# ProPrj_usb__2025-12-14-12-19-49.net
KiCad netlist of a schematic drawn in EasyEDA Pro
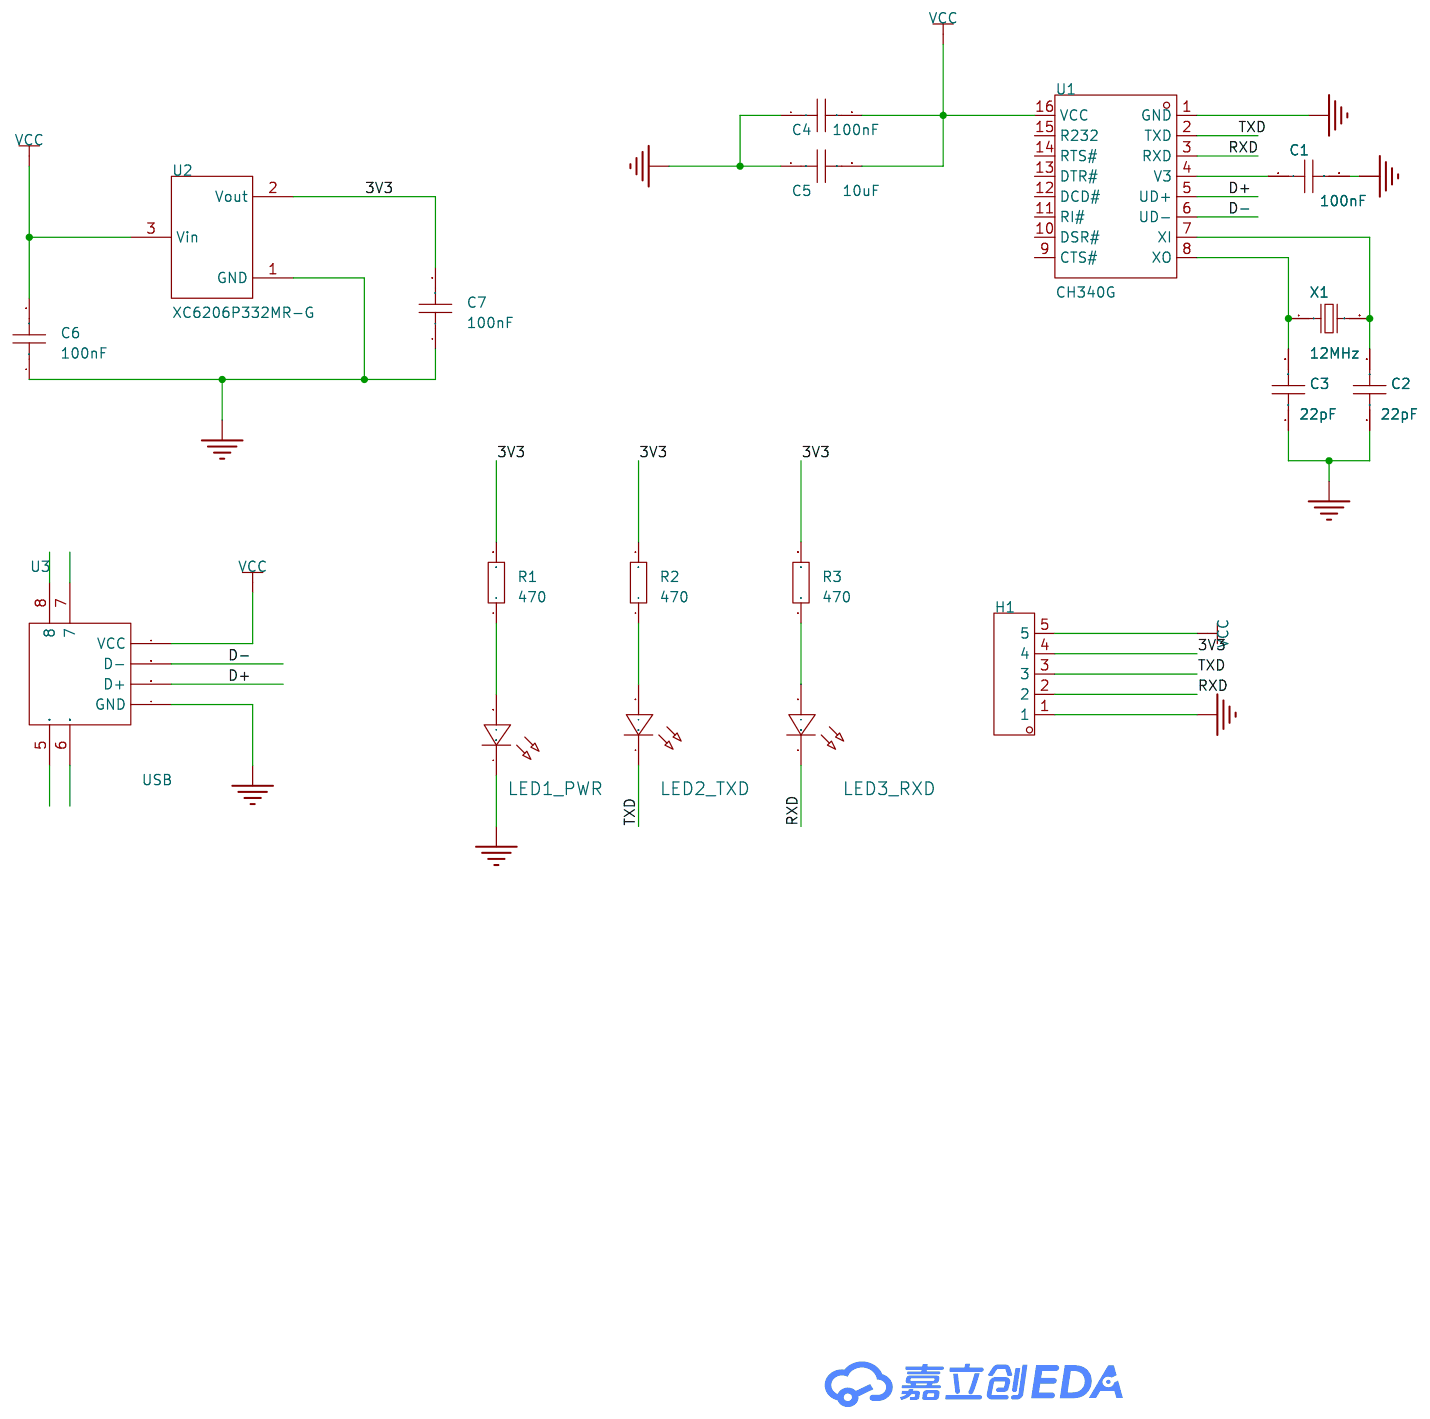
[diagram p0: schematic sheet]

(export (version "E")
  (design (tool "Eeschema 10.0.6"))
  (components
    (comp (ref "C1")
      (value "100nF")
      (footprint "easyedapro:C0603")
      (libsource (lib "easyedapro") (part "Capacitance"))
    )
    (comp (ref "C2")
      (value "22pF")
      (footprint "easyedapro:C0603")
      (libsource (lib "easyedapro") (part "Capacitance"))
    )
    (comp (ref "C3")
      (value "22pF")
      (footprint "easyedapro:C0603")
      (libsource (lib "easyedapro") (part "Capacitance"))
    )
    (comp (ref "C4")
      (value "100nF")
      (footprint "easyedapro:C0603")
      (libsource (lib "easyedapro") (part "Capacitance"))
    )
    (comp (ref "C5")
      (value "10uF")
      (footprint "easyedapro:C0603")
      (libsource (lib "easyedapro") (part "Capacitance"))
    )
    (comp (ref "C6")
      (value "100nF")
      (footprint "easyedapro:C0603")
      (libsource (lib "easyedapro") (part "Capacitance"))
    )
    (comp (ref "C7")
      (value "100nF")
      (footprint "easyedapro:C0603")
      (libsource (lib "easyedapro") (part "Capacitance"))
    )
    (comp (ref "H1")
      (value "~")
      (footprint "easyedapro:HDR-TH_5P-P2.54-V-M")
      (libsource (lib "easyedapro") (part "MTP125-1105S1"))
    )
    (comp (ref "LED1_PWR")
      (value "~")
      (footprint "easyedapro:LED_0603")
      (libsource (lib "easyedapro") (part "LED_R"))
    )
    (comp (ref "LED2_TXD")
      (value "~")
      (footprint "easyedapro:LED_0603")
      (libsource (lib "easyedapro") (part "LED_R"))
    )
    (comp (ref "LED3_RXD")
      (value "~")
      (footprint "easyedapro:LED_0603")
      (libsource (lib "easyedapro") (part "LED_R"))
    )
    (comp (ref "R1") (value "470") (footprint "easyedapro:R0603") (libsource (lib "easyedapro") (part "电阻")))
    (comp (ref "R2") (value "470") (footprint "easyedapro:R0603") (libsource (lib "easyedapro") (part "电阻")))
    (comp (ref "R3") (value "470") (footprint "easyedapro:R0603") (libsource (lib "easyedapro") (part "电阻")))
    (comp (ref "U1")
      (value "CH340G")
      (footprint "easyedapro:SOIC-16_L9.9-W3.9-P1.27-LS6.0-BL")
      (description "应用功能:USB转UART;接口协议:USB 2.0;数据速率:2Mbps;")
      (fields (field (name "Manufacturer") "WCH(南京沁恒)"))
      (libsource (lib "easyedapro") (part "CH340G"))
    )
    (comp (ref "U2")
      (value "XC6206P332MR-G")
      (footprint "easyedapro:SOT-23-3_L2.9-W1.6-P1.90-LS2.8-BR")
      (description "输出类型:固定;工作电压:6V;输出电压:3.3V;输出电流:200mA;电源纹波抑制比(PSRR):-;输出极性:正极;")
      (fields (field (name "Manufacturer") "TOREX(特瑞仕)"))
      (libsource (lib "easyedapro") (part "XC6206P332MR"))
    )
    (comp (ref "U3")
      (value "USB")
      (footprint "easyedapro:USB-SMD_USB_1")
      (libsource (lib "easyedapro") (part "USB"))
    )
    (comp (ref "X1")
      (value "12MHz")
      (footprint "easyedapro:CRYSTAL-SMD_L5.0-W3.2")
      (description "晶振类型:贴片晶振;频率:12MHz;常温频差:±20ppm;负载电容:20pF;频率稳定度:±30ppm;")
      (fields
        (field (name "Manufacturer Part") "XC53G2-12.000-F20LJDT")
        (field (name "Manufacturer") "HCI(杭晶)")
      )
      (libsource (lib "easyedapro") (part "XC53G2-12.000-F20LJDT"))
    )
  )
  (nets
    (net (code "1") (name "/3V3") (class "Default")
      (node (ref "C7") (pin "2") (pinfunction "2_2") (pintype "input"))
      (node (ref "H1") (pin "4") (pinfunction "4_4") (pintype "unspecified"))
      (node (ref "R1") (pin "2") (pinfunction "2_2") (pintype "input"))
      (node (ref "R2") (pin "2") (pinfunction "2_2") (pintype "input"))
      (node (ref "R3") (pin "2") (pinfunction "2_2") (pintype "input"))
      (node (ref "U2") (pin "2") (pinfunction "Vout_2") (pintype "unspecified"))
    )
    (net (code "2") (name "/D+") (class "Default")
      (node (ref "U1") (pin "5") (pinfunction "UD+_5") (pintype "unspecified"))
      (node (ref "U3") (pin "3") (pinfunction "D+_3") (pintype "input"))
    )
    (net (code "3") (name "/D-") (class "Default")
      (node (ref "U1") (pin "6") (pinfunction "UD-_6") (pintype "unspecified"))
      (node (ref "U3") (pin "2") (pinfunction "D-_2") (pintype "input"))
    )
    (net (code "4") (name "/RXD") (class "Default")
      (node (ref "H1") (pin "2") (pinfunction "2_2") (pintype "unspecified"))
      (node (ref "LED3_RXD") (pin "1") (pinfunction "C_1") (pintype "input"))
      (node (ref "U1") (pin "3") (pinfunction "RXD_3") (pintype "unspecified"))
    )
    (net (code "5") (name "/TXD") (class "Default")
      (node (ref "H1") (pin "3") (pinfunction "3_3") (pintype "unspecified"))
      (node (ref "LED2_TXD") (pin "1") (pinfunction "C_1") (pintype "input"))
      (node (ref "U1") (pin "2") (pinfunction "TXD_2") (pintype "unspecified"))
    )
    (net (code "6") (name "GND") (class "Default")
      (node (ref "C1") (pin "2") (pinfunction "2_2") (pintype "input"))
      (node (ref "C2") (pin "1") (pinfunction "1_1") (pintype "input"))
      (node (ref "C3") (pin "1") (pinfunction "1_1") (pintype "input"))
      (node (ref "C4") (pin "1") (pinfunction "1_1") (pintype "input"))
      (node (ref "C5") (pin "1") (pinfunction "1_1") (pintype "input"))
      (node (ref "C6") (pin "1") (pinfunction "1_1") (pintype "input"))
      (node (ref "C7") (pin "1") (pinfunction "1_1") (pintype "input"))
      (node (ref "H1") (pin "1") (pinfunction "1_1") (pintype "unspecified"))
      (node (ref "LED1_PWR") (pin "1") (pinfunction "C_1") (pintype "input"))
      (node (ref "U1") (pin "1") (pinfunction "GND_1") (pintype "unspecified"))
      (node (ref "U2") (pin "1") (pinfunction "GND_1") (pintype "unspecified"))
      (node (ref "U3") (pin "4") (pinfunction "GND_4") (pintype "input"))
    )
    (net (code "7") (name "Net-(LED1_PWR-A)") (class "Default")
      (node (ref "LED1_PWR") (pin "2") (pinfunction "A_2") (pintype "input"))
      (node (ref "R1") (pin "1") (pinfunction "1_1") (pintype "input"))
    )
    (net (code "8") (name "Net-(LED2_TXD-A)") (class "Default")
      (node (ref "LED2_TXD") (pin "2") (pinfunction "A_2") (pintype "input"))
      (node (ref "R2") (pin "1") (pinfunction "1_1") (pintype "input"))
    )
    (net (code "9") (name "Net-(LED3_RXD-A)") (class "Default")
      (node (ref "LED3_RXD") (pin "2") (pinfunction "A_2") (pintype "input"))
      (node (ref "R3") (pin "1") (pinfunction "1_1") (pintype "input"))
    )
    (net (code "10") (name "Net-(U1-V3)") (class "Default")
      (node (ref "C1") (pin "1") (pinfunction "1_1") (pintype "input"))
      (node (ref "U1") (pin "4") (pinfunction "V3_4") (pintype "unspecified"))
    )
    (net (code "11") (name "Net-(U1-XI)") (class "Default")
      (node (ref "C2") (pin "2") (pinfunction "2_2") (pintype "input"))
      (node (ref "U1") (pin "7") (pinfunction "XI_7") (pintype "unspecified"))
      (node (ref "X1") (pin "2") (pinfunction "2_2") (pintype "unspecified"))
    )
    (net (code "12") (name "Net-(U1-XO)") (class "Default")
      (node (ref "C3") (pin "2") (pinfunction "2_2") (pintype "input"))
      (node (ref "U1") (pin "8") (pinfunction "XO_8") (pintype "unspecified"))
      (node (ref "X1") (pin "1") (pinfunction "1_1") (pintype "unspecified"))
    )
    (net (code "13") (name "VCC") (class "Default")
      (node (ref "C4") (pin "2") (pinfunction "2_2") (pintype "input"))
      (node (ref "C5") (pin "2") (pinfunction "2_2") (pintype "input"))
      (node (ref "C6") (pin "2") (pinfunction "2_2") (pintype "input"))
      (node (ref "H1") (pin "5") (pinfunction "5_5") (pintype "unspecified"))
      (node (ref "U1") (pin "16") (pinfunction "VCC_16") (pintype "unspecified"))
      (node (ref "U2") (pin "3") (pinfunction "Vin_3") (pintype "unspecified"))
      (node (ref "U3") (pin "1") (pinfunction "VCC_1") (pintype "input"))
    )
    (net (code "14") (name "unconnected-(U1-CTS#-Pad9)") (class "Default")
      (node (ref "U1") (pin "9") (pinfunction "CTS#_9") (pintype "unspecified"))
    )
    (net (code "15") (name "unconnected-(U1-DCD#-Pad12)") (class "Default")
      (node (ref "U1") (pin "12") (pinfunction "DCD#_12") (pintype "unspecified"))
    )
    (net (code "16") (name "unconnected-(U1-DSR#-Pad10)") (class "Default")
      (node (ref "U1") (pin "10") (pinfunction "DSR#_10") (pintype "unspecified"))
    )
    (net (code "17") (name "unconnected-(U1-DTR#-Pad13)") (class "Default")
      (node (ref "U1") (pin "13") (pinfunction "DTR#_13") (pintype "unspecified"))
    )
    (net (code "18") (name "unconnected-(U1-R232-Pad15)") (class "Default")
      (node (ref "U1") (pin "15") (pinfunction "R232_15") (pintype "unspecified"))
    )
    (net (code "19") (name "unconnected-(U1-RI#-Pad11)") (class "Default")
      (node (ref "U1") (pin "11") (pinfunction "RI#_11") (pintype "unspecified"))
    )
    (net (code "20") (name "unconnected-(U1-RTS#-Pad14)") (class "Default")
      (node (ref "U1") (pin "14") (pinfunction "RTS#_14") (pintype "unspecified"))
    )
    (net (code "21") (name "unconnected-(U3-Pad7)") (class "Default")
      (node (ref "U3") (pin "7") (pinfunction "7_7") (pintype "unspecified"))
    )
    (net (code "22") (name "unconnected-(U3-Pad8)") (class "Default")
      (node (ref "U3") (pin "8") (pinfunction "8_8") (pintype "unspecified"))
    )
    (net (code "23") (name "unconnected-(U3-SH1-Pad5)") (class "Default")
      (node (ref "U3") (pin "5") (pinfunction "SH1_5") (pintype "unspecified"))
    )
    (net (code "24") (name "unconnected-(U3-SH2-Pad6)") (class "Default")
      (node (ref "U3") (pin "6") (pinfunction "SH2_6") (pintype "unspecified"))
    )
  )
)
